# Wheel_speed_tester_rev1.net
KiCad netlist of a schematic drawn in EAGLE
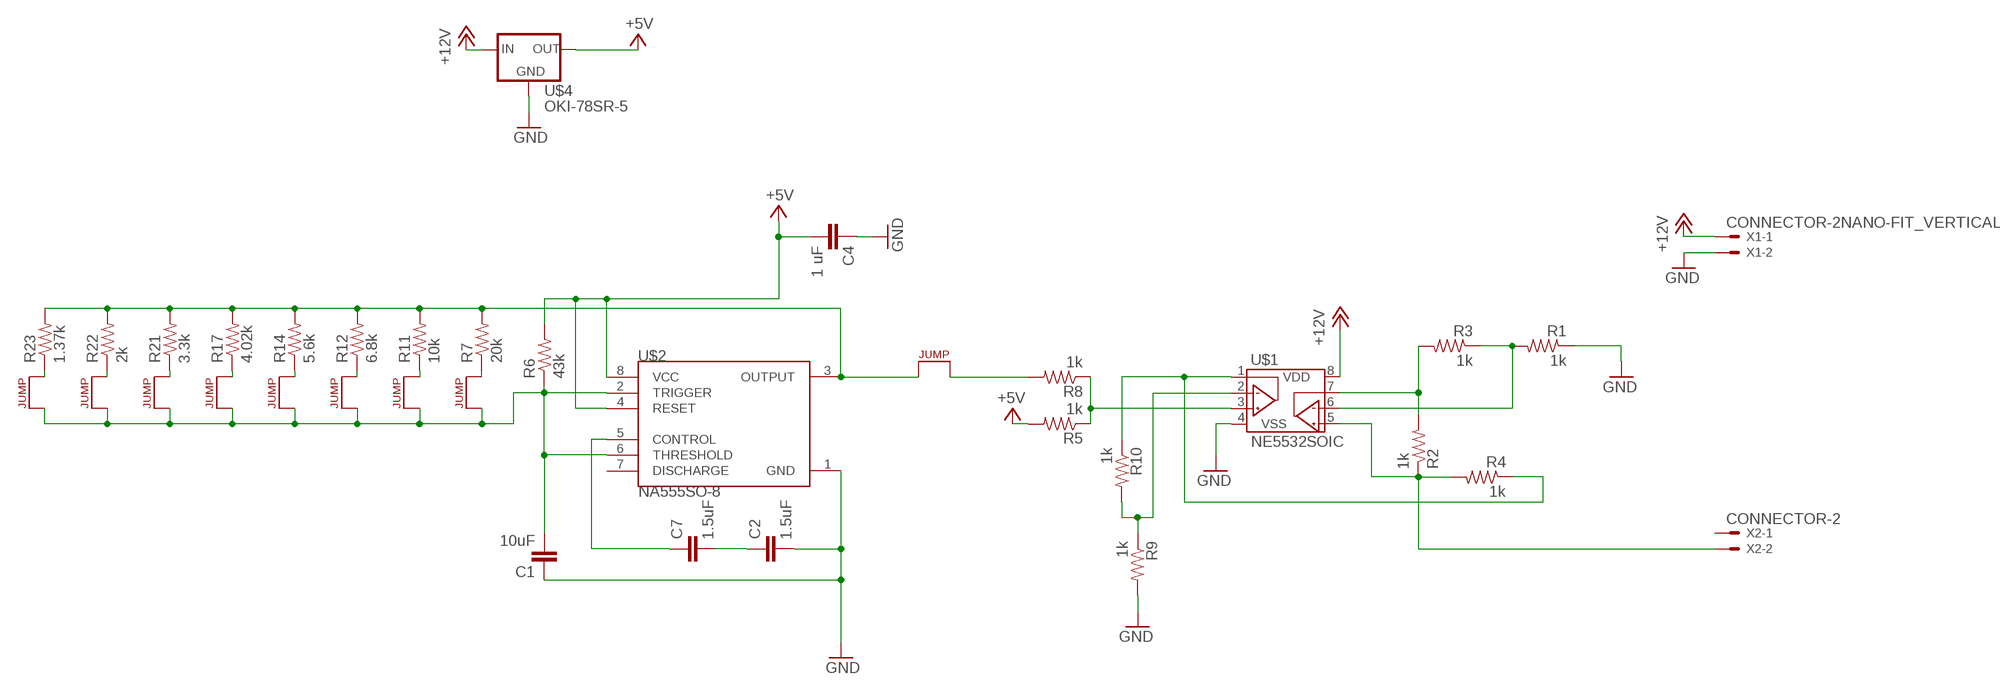
[diagram p0: schematic, sheet 1, part 1 of 2]
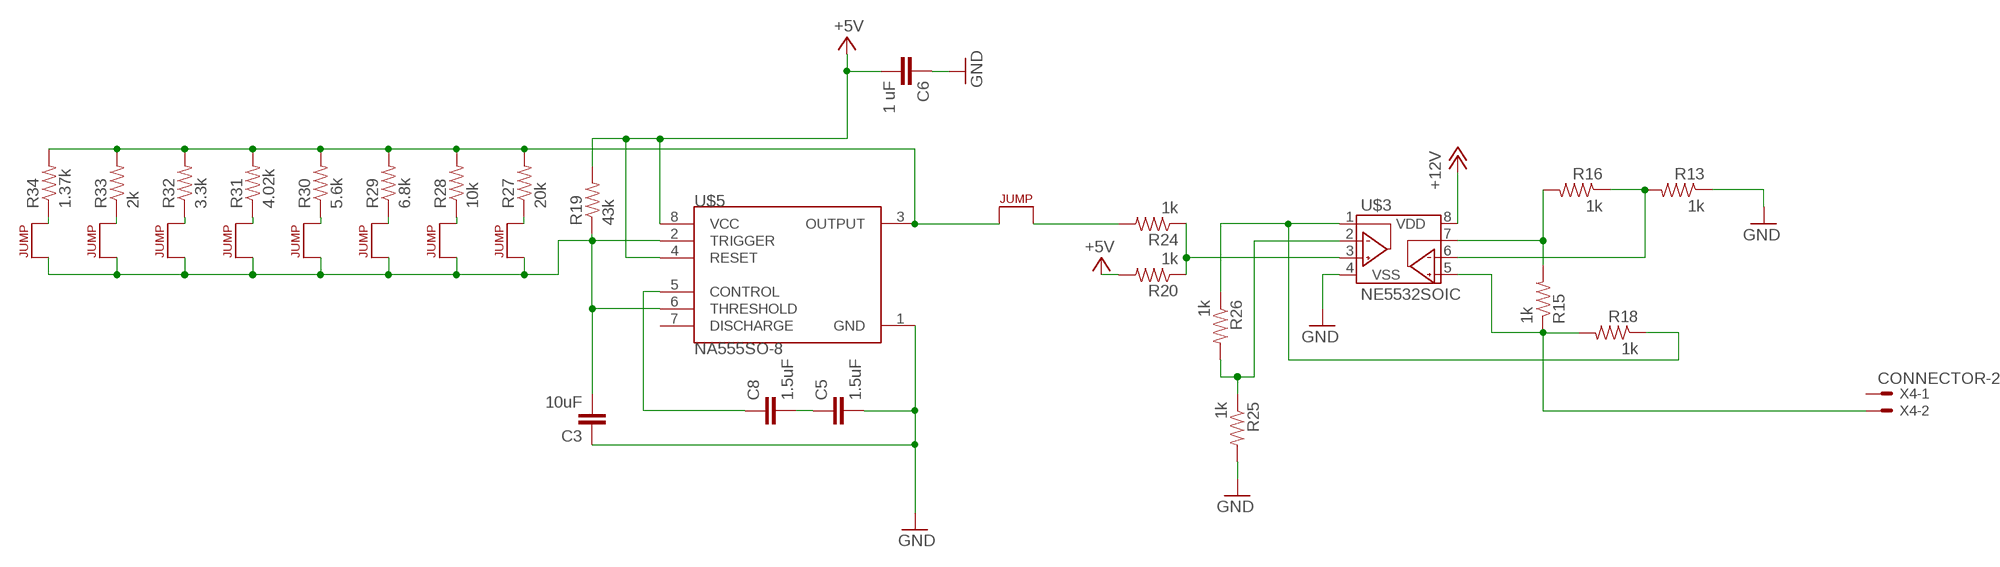
[diagram p1: schematic, sheet 1, part 2 of 2]

(export (version "E")
  (design (tool "Eeschema 10.0.6"))
  (components
    (comp (ref "C1")
      (value "10uF")
      (footprint "eagle-import:0603-CAP")
      (libsource (lib "eagle-import") (part "CAP0603-CAP"))
    )
    (comp (ref "C2")
      (value "1.5uF")
      (footprint "eagle-import:0603-CAP")
      (libsource (lib "eagle-import") (part "CAP0603-CAP"))
    )
    (comp (ref "C3")
      (value "10uF")
      (footprint "eagle-import:0603-CAP")
      (libsource (lib "eagle-import") (part "CAP0603-CAP"))
    )
    (comp (ref "C4")
      (value "1 uF")
      (footprint "eagle-import:0603-CAP")
      (libsource (lib "eagle-import") (part "CAP0603-CAP"))
    )
    (comp (ref "C5")
      (value "1.5uF")
      (footprint "eagle-import:0603-CAP")
      (libsource (lib "eagle-import") (part "CAP0603-CAP"))
    )
    (comp (ref "C6")
      (value "1 uF")
      (footprint "eagle-import:0603-CAP")
      (libsource (lib "eagle-import") (part "CAP0603-CAP"))
    )
    (comp (ref "C7")
      (value "1.5uF")
      (footprint "eagle-import:0603-CAP")
      (libsource (lib "eagle-import") (part "CAP0603-CAP"))
    )
    (comp (ref "C8")
      (value "1.5uF")
      (footprint "eagle-import:0603-CAP")
      (libsource (lib "eagle-import") (part "CAP0603-CAP"))
    )
    (comp (ref "J1")
      (value "JUMPER.1")
      (footprint "eagle-import:1X02")
      (libsource (lib "eagle-import") (part "JUMPER.1"))
    )
    (comp (ref "J2")
      (value "JUMPER.1")
      (footprint "eagle-import:1X02")
      (libsource (lib "eagle-import") (part "JUMPER.1"))
    )
    (comp (ref "J3")
      (value "JUMPER.1")
      (footprint "eagle-import:1X02")
      (libsource (lib "eagle-import") (part "JUMPER.1"))
    )
    (comp (ref "J4")
      (value "JUMPER.1")
      (footprint "eagle-import:1X02")
      (libsource (lib "eagle-import") (part "JUMPER.1"))
    )
    (comp (ref "J5")
      (value "JUMPER.1")
      (footprint "eagle-import:1X02")
      (libsource (lib "eagle-import") (part "JUMPER.1"))
    )
    (comp (ref "J6")
      (value "JUMPER.1")
      (footprint "eagle-import:1X02")
      (libsource (lib "eagle-import") (part "JUMPER.1"))
    )
    (comp (ref "J7")
      (value "JUMPER.1")
      (footprint "eagle-import:1X02")
      (libsource (lib "eagle-import") (part "JUMPER.1"))
    )
    (comp (ref "J8")
      (value "JUMPER.1")
      (footprint "eagle-import:1X02")
      (libsource (lib "eagle-import") (part "JUMPER.1"))
    )
    (comp (ref "J9")
      (value "JUMPER.1")
      (footprint "eagle-import:1X02")
      (libsource (lib "eagle-import") (part "JUMPER.1"))
    )
    (comp (ref "J10")
      (value "JUMPER.1")
      (footprint "eagle-import:1X02")
      (libsource (lib "eagle-import") (part "JUMPER.1"))
    )
    (comp (ref "J11")
      (value "JUMPER.1")
      (footprint "eagle-import:1X02")
      (libsource (lib "eagle-import") (part "JUMPER.1"))
    )
    (comp (ref "J12")
      (value "JUMPER.1")
      (footprint "eagle-import:1X02")
      (libsource (lib "eagle-import") (part "JUMPER.1"))
    )
    (comp (ref "J13")
      (value "JUMPER.1")
      (footprint "eagle-import:1X02")
      (libsource (lib "eagle-import") (part "JUMPER.1"))
    )
    (comp (ref "J14")
      (value "JUMPER.1")
      (footprint "eagle-import:1X02")
      (libsource (lib "eagle-import") (part "JUMPER.1"))
    )
    (comp (ref "J15")
      (value "JUMPER.1")
      (footprint "eagle-import:1X02")
      (libsource (lib "eagle-import") (part "JUMPER.1"))
    )
    (comp (ref "J16")
      (value "JUMPER.1")
      (footprint "eagle-import:1X02")
      (libsource (lib "eagle-import") (part "JUMPER.1"))
    )
    (comp (ref "J17")
      (value "JUMPER.1")
      (footprint "eagle-import:1X02")
      (libsource (lib "eagle-import") (part "JUMPER.1"))
    )
    (comp (ref "J18")
      (value "JUMPER.1")
      (footprint "eagle-import:1X02")
      (libsource (lib "eagle-import") (part "JUMPER.1"))
    )
    (comp (ref "R1")
      (value "1k")
      (footprint "eagle-import:0603-RES")
      (libsource (lib "eagle-import") (part "RESISTOR0603"))
    )
    (comp (ref "R2")
      (value "1k")
      (footprint "eagle-import:0603-RES")
      (libsource (lib "eagle-import") (part "RESISTOR0603"))
    )
    (comp (ref "R3")
      (value "1k")
      (footprint "eagle-import:0603-RES")
      (libsource (lib "eagle-import") (part "RESISTOR0603"))
    )
    (comp (ref "R4")
      (value "1k")
      (footprint "eagle-import:0603-RES")
      (libsource (lib "eagle-import") (part "RESISTOR0603"))
    )
    (comp (ref "R5")
      (value "1k")
      (footprint "eagle-import:0603-RES")
      (libsource (lib "eagle-import") (part "RESISTOR0603"))
    )
    (comp (ref "R6")
      (value "43k")
      (footprint "eagle-import:0603-RES")
      (libsource (lib "eagle-import") (part "RESISTOR0603"))
    )
    (comp (ref "R7")
      (value "20k")
      (footprint "eagle-import:0603-RES")
      (libsource (lib "eagle-import") (part "RESISTOR0603"))
    )
    (comp (ref "R8")
      (value "1k")
      (footprint "eagle-import:0603-RES")
      (libsource (lib "eagle-import") (part "RESISTOR0603"))
    )
    (comp (ref "R9")
      (value "1k")
      (footprint "eagle-import:0603-RES")
      (libsource (lib "eagle-import") (part "RESISTOR0603"))
    )
    (comp (ref "R10")
      (value "1k")
      (footprint "eagle-import:0603-RES")
      (libsource (lib "eagle-import") (part "RESISTOR0603"))
    )
    (comp (ref "R11")
      (value "10k")
      (footprint "eagle-import:0603-RES")
      (libsource (lib "eagle-import") (part "RESISTOR0603"))
    )
    (comp (ref "R12")
      (value "6.8k")
      (footprint "eagle-import:0603-RES")
      (libsource (lib "eagle-import") (part "RESISTOR0603"))
    )
    (comp (ref "R13")
      (value "1k")
      (footprint "eagle-import:0603-RES")
      (libsource (lib "eagle-import") (part "RESISTOR0603"))
    )
    (comp (ref "R14")
      (value "5.6k")
      (footprint "eagle-import:0603-RES")
      (libsource (lib "eagle-import") (part "RESISTOR0603"))
    )
    (comp (ref "R15")
      (value "1k")
      (footprint "eagle-import:0603-RES")
      (libsource (lib "eagle-import") (part "RESISTOR0603"))
    )
    (comp (ref "R16")
      (value "1k")
      (footprint "eagle-import:0603-RES")
      (libsource (lib "eagle-import") (part "RESISTOR0603"))
    )
    (comp (ref "R17")
      (value "4.02k")
      (footprint "eagle-import:0603-RES")
      (libsource (lib "eagle-import") (part "RESISTOR0603"))
    )
    (comp (ref "R18")
      (value "1k")
      (footprint "eagle-import:0603-RES")
      (libsource (lib "eagle-import") (part "RESISTOR0603"))
    )
    (comp (ref "R19")
      (value "43k")
      (footprint "eagle-import:0603-RES")
      (libsource (lib "eagle-import") (part "RESISTOR0603"))
    )
    (comp (ref "R20")
      (value "1k")
      (footprint "eagle-import:0603-RES")
      (libsource (lib "eagle-import") (part "RESISTOR0603"))
    )
    (comp (ref "R21")
      (value "3.3k")
      (footprint "eagle-import:0603-RES")
      (libsource (lib "eagle-import") (part "RESISTOR0603"))
    )
    (comp (ref "R22")
      (value "2k")
      (footprint "eagle-import:0603-RES")
      (libsource (lib "eagle-import") (part "RESISTOR0603"))
    )
    (comp (ref "R23")
      (value "1.37k")
      (footprint "eagle-import:0603-RES")
      (libsource (lib "eagle-import") (part "RESISTOR0603"))
    )
    (comp (ref "R24")
      (value "1k")
      (footprint "eagle-import:0603-RES")
      (libsource (lib "eagle-import") (part "RESISTOR0603"))
    )
    (comp (ref "R25")
      (value "1k")
      (footprint "eagle-import:0603-RES")
      (libsource (lib "eagle-import") (part "RESISTOR0603"))
    )
    (comp (ref "R26")
      (value "1k")
      (footprint "eagle-import:0603-RES")
      (libsource (lib "eagle-import") (part "RESISTOR0603"))
    )
    (comp (ref "R27")
      (value "20k")
      (footprint "eagle-import:0603-RES")
      (libsource (lib "eagle-import") (part "RESISTOR0603"))
    )
    (comp (ref "R28")
      (value "10k")
      (footprint "eagle-import:0603-RES")
      (libsource (lib "eagle-import") (part "RESISTOR0603"))
    )
    (comp (ref "R29")
      (value "6.8k")
      (footprint "eagle-import:0603-RES")
      (libsource (lib "eagle-import") (part "RESISTOR0603"))
    )
    (comp (ref "R30")
      (value "5.6k")
      (footprint "eagle-import:0603-RES")
      (libsource (lib "eagle-import") (part "RESISTOR0603"))
    )
    (comp (ref "R31")
      (value "4.02k")
      (footprint "eagle-import:0603-RES")
      (libsource (lib "eagle-import") (part "RESISTOR0603"))
    )
    (comp (ref "R32")
      (value "3.3k")
      (footprint "eagle-import:0603-RES")
      (libsource (lib "eagle-import") (part "RESISTOR0603"))
    )
    (comp (ref "R33")
      (value "2k")
      (footprint "eagle-import:0603-RES")
      (libsource (lib "eagle-import") (part "RESISTOR0603"))
    )
    (comp (ref "R34")
      (value "1.37k")
      (footprint "eagle-import:0603-RES")
      (libsource (lib "eagle-import") (part "RESISTOR0603"))
    )
    (comp (ref "U$1")
      (value "NE5532SOIC")
      (footprint "eagle-import:SOIC-08")
      (libsource (lib "eagle-import") (part "NE5532SOIC"))
    )
    (comp (ref "U$2")
      (value "NA555SO-8")
      (footprint "eagle-import:SOIC-08")
      (libsource (lib "eagle-import") (part "NA555SO-8"))
    )
    (comp (ref "U$3")
      (value "NE5532SOIC")
      (footprint "eagle-import:SOIC-08")
      (libsource (lib "eagle-import") (part "NE5532SOIC"))
    )
    (comp (ref "U$4")
      (value "OKI-78SR-5")
      (footprint "eagle-import:OKI-78SR")
      (libsource (lib "eagle-import") (part "OKI-78SR-5"))
    )
    (comp (ref "U$5")
      (value "NA555SO-8")
      (footprint "eagle-import:SOIC-08")
      (libsource (lib "eagle-import") (part "NA555SO-8"))
    )
    (comp (ref "X1")
      (value "CONNECTOR-2NANO-FIT_VERTICAL-2")
      (footprint "eagle-import:NANO-FIT_VERTICAL-2")
      (libsource (lib "eagle-import") (part "CONNECTOR-2NANO-FIT_VERTICAL-2"))
    )
    (comp (ref "X2")
      (value "CONNECTOR-2")
      (footprint "eagle-import:MINIFIT_5566-2")
      (libsource (lib "eagle-import") (part "CONNECTOR-2"))
    )
    (comp (ref "X4")
      (value "CONNECTOR-2")
      (footprint "eagle-import:MINIFIT_5566-2")
      (libsource (lib "eagle-import") (part "CONNECTOR-2"))
    )
  )
  (nets
    (net (code "1") (name "+5V") (class "Default")
      (node (ref "C4") (pin "2") (pinfunction "2_2") (pintype "passive"))
      (node (ref "C6") (pin "2") (pinfunction "2_2") (pintype "passive"))
      (node (ref "R19") (pin "2") (pinfunction "2_2") (pintype "passive"))
      (node (ref "R20") (pin "2") (pinfunction "2_2") (pintype "passive"))
      (node (ref "R5") (pin "2") (pinfunction "2_2") (pintype "passive"))
      (node (ref "R6") (pin "2") (pinfunction "2_2") (pintype "passive"))
      (node (ref "U$2") (pin "4") (pinfunction "RESET_4") (pintype "passive"))
      (node (ref "U$2") (pin "8") (pinfunction "VCC_8") (pintype "passive"))
      (node (ref "U$4") (pin "3") (pinfunction "OUT_3") (pintype "output"))
      (node (ref "U$5") (pin "4") (pinfunction "RESET_4") (pintype "passive"))
      (node (ref "U$5") (pin "8") (pinfunction "VCC_8") (pintype "passive"))
    )
    (net (code "2") (name "+12V") (class "Default")
      (node (ref "U$1") (pin "8") (pinfunction "VDD_8") (pintype "passive"))
      (node (ref "U$3") (pin "8") (pinfunction "VDD_8") (pintype "passive"))
      (node (ref "U$4") (pin "1") (pinfunction "IN_1") (pintype "input"))
      (node (ref "X1") (pin "P$1") (pinfunction "S_P$1") (pintype "passive"))
    )
    (net (code "3") (name "GND") (class "Default")
      (node (ref "C1") (pin "1") (pinfunction "1_1") (pintype "passive"))
      (node (ref "C2") (pin "2") (pinfunction "2_2") (pintype "passive"))
      (node (ref "C3") (pin "1") (pinfunction "1_1") (pintype "passive"))
      (node (ref "C4") (pin "1") (pinfunction "1_1") (pintype "passive"))
      (node (ref "C5") (pin "2") (pinfunction "2_2") (pintype "passive"))
      (node (ref "C6") (pin "1") (pinfunction "1_1") (pintype "passive"))
      (node (ref "R1") (pin "1") (pinfunction "1_1") (pintype "passive"))
      (node (ref "R13") (pin "1") (pinfunction "1_1") (pintype "passive"))
      (node (ref "R25") (pin "2") (pinfunction "2_2") (pintype "passive"))
      (node (ref "R9") (pin "2") (pinfunction "2_2") (pintype "passive"))
      (node (ref "U$1") (pin "4") (pinfunction "VSS_4") (pintype "passive"))
      (node (ref "U$2") (pin "1") (pinfunction "GND_1") (pintype "passive"))
      (node (ref "U$3") (pin "4") (pinfunction "VSS_4") (pintype "passive"))
      (node (ref "U$4") (pin "2") (pinfunction "GND_2") (pintype "input"))
      (node (ref "U$5") (pin "1") (pinfunction "GND_1") (pintype "passive"))
      (node (ref "X1") (pin "P$2") (pinfunction "S_P$2") (pintype "passive"))
    )
    (net (code "4") (name "Net-(C2-Pad1)") (class "Default")
      (node (ref "C2") (pin "1") (pinfunction "1_1") (pintype "passive"))
      (node (ref "C7") (pin "2") (pinfunction "2_2") (pintype "passive"))
    )
    (net (code "5") (name "Net-(C5-Pad1)") (class "Default")
      (node (ref "C5") (pin "1") (pinfunction "1_1") (pintype "passive"))
      (node (ref "C8") (pin "2") (pinfunction "2_2") (pintype "passive"))
    )
    (net (code "6") (name "Net-(J1-P$1)") (class "Default")
      (node (ref "C1") (pin "2") (pinfunction "2_2") (pintype "passive"))
      (node (ref "J1") (pin "1") (pinfunction "P$1_1") (pintype "bidirectional"))
      (node (ref "J3") (pin "1") (pinfunction "P$1_1") (pintype "bidirectional"))
      (node (ref "J4") (pin "1") (pinfunction "P$1_1") (pintype "bidirectional"))
      (node (ref "J5") (pin "1") (pinfunction "P$1_1") (pintype "bidirectional"))
      (node (ref "J6") (pin "1") (pinfunction "P$1_1") (pintype "bidirectional"))
      (node (ref "J7") (pin "1") (pinfunction "P$1_1") (pintype "bidirectional"))
      (node (ref "J8") (pin "1") (pinfunction "P$1_1") (pintype "bidirectional"))
      (node (ref "J9") (pin "1") (pinfunction "P$1_1") (pintype "bidirectional"))
      (node (ref "R6") (pin "1") (pinfunction "1_1") (pintype "passive"))
      (node (ref "U$2") (pin "2") (pinfunction "TRIGGER_2") (pintype "passive"))
      (node (ref "U$2") (pin "6") (pinfunction "THRESHOLD_6") (pintype "passive"))
    )
    (net (code "7") (name "Net-(J1-P$2)") (class "Default")
      (node (ref "J1") (pin "2") (pinfunction "P$2_2") (pintype "bidirectional"))
      (node (ref "R23") (pin "1") (pinfunction "1_1") (pintype "passive"))
    )
    (net (code "8") (name "Net-(J2-P$1)") (class "Default")
      (node (ref "J2") (pin "1") (pinfunction "P$1_1") (pintype "bidirectional"))
      (node (ref "R11") (pin "2") (pinfunction "2_2") (pintype "passive"))
      (node (ref "R12") (pin "2") (pinfunction "2_2") (pintype "passive"))
      (node (ref "R14") (pin "2") (pinfunction "2_2") (pintype "passive"))
      (node (ref "R17") (pin "2") (pinfunction "2_2") (pintype "passive"))
      (node (ref "R21") (pin "2") (pinfunction "2_2") (pintype "passive"))
      (node (ref "R22") (pin "2") (pinfunction "2_2") (pintype "passive"))
      (node (ref "R23") (pin "2") (pinfunction "2_2") (pintype "passive"))
      (node (ref "R7") (pin "2") (pinfunction "2_2") (pintype "passive"))
      (node (ref "U$2") (pin "3") (pinfunction "OUTPUT_3") (pintype "passive"))
    )
    (net (code "9") (name "Net-(J2-P$2)") (class "Default")
      (node (ref "J2") (pin "2") (pinfunction "P$2_2") (pintype "bidirectional"))
      (node (ref "R8") (pin "2") (pinfunction "2_2") (pintype "passive"))
    )
    (net (code "10") (name "Net-(J3-P$2)") (class "Default")
      (node (ref "J3") (pin "2") (pinfunction "P$2_2") (pintype "bidirectional"))
      (node (ref "R22") (pin "1") (pinfunction "1_1") (pintype "passive"))
    )
    (net (code "11") (name "Net-(J4-P$2)") (class "Default")
      (node (ref "J4") (pin "2") (pinfunction "P$2_2") (pintype "bidirectional"))
      (node (ref "R21") (pin "1") (pinfunction "1_1") (pintype "passive"))
    )
    (net (code "12") (name "Net-(J5-P$2)") (class "Default")
      (node (ref "J5") (pin "2") (pinfunction "P$2_2") (pintype "bidirectional"))
      (node (ref "R17") (pin "1") (pinfunction "1_1") (pintype "passive"))
    )
    (net (code "13") (name "Net-(J6-P$2)") (class "Default")
      (node (ref "J6") (pin "2") (pinfunction "P$2_2") (pintype "bidirectional"))
      (node (ref "R14") (pin "1") (pinfunction "1_1") (pintype "passive"))
    )
    (net (code "14") (name "Net-(J7-P$2)") (class "Default")
      (node (ref "J7") (pin "2") (pinfunction "P$2_2") (pintype "bidirectional"))
      (node (ref "R12") (pin "1") (pinfunction "1_1") (pintype "passive"))
    )
    (net (code "15") (name "Net-(J8-P$2)") (class "Default")
      (node (ref "J8") (pin "2") (pinfunction "P$2_2") (pintype "bidirectional"))
      (node (ref "R11") (pin "1") (pinfunction "1_1") (pintype "passive"))
    )
    (net (code "16") (name "Net-(J9-P$2)") (class "Default")
      (node (ref "J9") (pin "2") (pinfunction "P$2_2") (pintype "bidirectional"))
      (node (ref "R7") (pin "1") (pinfunction "1_1") (pintype "passive"))
    )
    (net (code "17") (name "Net-(J10-P$1)") (class "Default")
      (node (ref "J10") (pin "1") (pinfunction "P$1_1") (pintype "bidirectional"))
      (node (ref "R27") (pin "2") (pinfunction "2_2") (pintype "passive"))
      (node (ref "R28") (pin "2") (pinfunction "2_2") (pintype "passive"))
      (node (ref "R29") (pin "2") (pinfunction "2_2") (pintype "passive"))
      (node (ref "R30") (pin "2") (pinfunction "2_2") (pintype "passive"))
      (node (ref "R31") (pin "2") (pinfunction "2_2") (pintype "passive"))
      (node (ref "R32") (pin "2") (pinfunction "2_2") (pintype "passive"))
      (node (ref "R33") (pin "2") (pinfunction "2_2") (pintype "passive"))
      (node (ref "R34") (pin "2") (pinfunction "2_2") (pintype "passive"))
      (node (ref "U$5") (pin "3") (pinfunction "OUTPUT_3") (pintype "passive"))
    )
    (net (code "18") (name "Net-(J10-P$2)") (class "Default")
      (node (ref "J10") (pin "2") (pinfunction "P$2_2") (pintype "bidirectional"))
      (node (ref "R24") (pin "2") (pinfunction "2_2") (pintype "passive"))
    )
    (net (code "19") (name "Net-(J11-P$1)") (class "Default")
      (node (ref "C3") (pin "2") (pinfunction "2_2") (pintype "passive"))
      (node (ref "J11") (pin "1") (pinfunction "P$1_1") (pintype "bidirectional"))
      (node (ref "J12") (pin "1") (pinfunction "P$1_1") (pintype "bidirectional"))
      (node (ref "J13") (pin "1") (pinfunction "P$1_1") (pintype "bidirectional"))
      (node (ref "J14") (pin "1") (pinfunction "P$1_1") (pintype "bidirectional"))
      (node (ref "J15") (pin "1") (pinfunction "P$1_1") (pintype "bidirectional"))
      (node (ref "J16") (pin "1") (pinfunction "P$1_1") (pintype "bidirectional"))
      (node (ref "J17") (pin "1") (pinfunction "P$1_1") (pintype "bidirectional"))
      (node (ref "J18") (pin "1") (pinfunction "P$1_1") (pintype "bidirectional"))
      (node (ref "R19") (pin "1") (pinfunction "1_1") (pintype "passive"))
      (node (ref "U$5") (pin "2") (pinfunction "TRIGGER_2") (pintype "passive"))
      (node (ref "U$5") (pin "6") (pinfunction "THRESHOLD_6") (pintype "passive"))
    )
    (net (code "20") (name "Net-(J11-P$2)") (class "Default")
      (node (ref "J11") (pin "2") (pinfunction "P$2_2") (pintype "bidirectional"))
      (node (ref "R34") (pin "1") (pinfunction "1_1") (pintype "passive"))
    )
    (net (code "21") (name "Net-(J12-P$2)") (class "Default")
      (node (ref "J12") (pin "2") (pinfunction "P$2_2") (pintype "bidirectional"))
      (node (ref "R33") (pin "1") (pinfunction "1_1") (pintype "passive"))
    )
    (net (code "22") (name "Net-(J13-P$2)") (class "Default")
      (node (ref "J13") (pin "2") (pinfunction "P$2_2") (pintype "bidirectional"))
      (node (ref "R32") (pin "1") (pinfunction "1_1") (pintype "passive"))
    )
    (net (code "23") (name "Net-(J14-P$2)") (class "Default")
      (node (ref "J14") (pin "2") (pinfunction "P$2_2") (pintype "bidirectional"))
      (node (ref "R31") (pin "1") (pinfunction "1_1") (pintype "passive"))
    )
    (net (code "24") (name "Net-(J15-P$2)") (class "Default")
      (node (ref "J15") (pin "2") (pinfunction "P$2_2") (pintype "bidirectional"))
      (node (ref "R30") (pin "1") (pinfunction "1_1") (pintype "passive"))
    )
    (net (code "25") (name "Net-(J16-P$2)") (class "Default")
      (node (ref "J16") (pin "2") (pinfunction "P$2_2") (pintype "bidirectional"))
      (node (ref "R29") (pin "1") (pinfunction "1_1") (pintype "passive"))
    )
    (net (code "26") (name "Net-(J17-P$2)") (class "Default")
      (node (ref "J17") (pin "2") (pinfunction "P$2_2") (pintype "bidirectional"))
      (node (ref "R28") (pin "1") (pinfunction "1_1") (pintype "passive"))
    )
    (net (code "27") (name "Net-(J18-P$2)") (class "Default")
      (node (ref "J18") (pin "2") (pinfunction "P$2_2") (pintype "bidirectional"))
      (node (ref "R27") (pin "1") (pinfunction "1_1") (pintype "passive"))
    )
    (net (code "28") (name "Net-(U$1-VINA+)") (class "Default")
      (node (ref "R5") (pin "1") (pinfunction "1_1") (pintype "passive"))
      (node (ref "R8") (pin "1") (pinfunction "1_1") (pintype "passive"))
      (node (ref "U$1") (pin "3") (pinfunction "VINA+_3") (pintype "passive"))
    )
    (net (code "29") (name "Net-(U$1-VINA-)") (class "Default")
      (node (ref "R10") (pin "2") (pinfunction "2_2") (pintype "passive"))
      (node (ref "R9") (pin "1") (pinfunction "1_1") (pintype "passive"))
      (node (ref "U$1") (pin "2") (pinfunction "VINA-_2") (pintype "passive"))
    )
    (net (code "30") (name "Net-(U$1-VINB+)") (class "Default")
      (node (ref "R2") (pin "1") (pinfunction "1_1") (pintype "passive"))
      (node (ref "R4") (pin "2") (pinfunction "2_2") (pintype "passive"))
      (node (ref "U$1") (pin "5") (pinfunction "VINB+_5") (pintype "passive"))
      (node (ref "X2") (pin "2") (pinfunction "S_2") (pintype "passive"))
    )
    (net (code "31") (name "Net-(U$1-VINB-)") (class "Default")
      (node (ref "R1") (pin "2") (pinfunction "2_2") (pintype "passive"))
      (node (ref "R3") (pin "1") (pinfunction "1_1") (pintype "passive"))
      (node (ref "U$1") (pin "6") (pinfunction "VINB-_6") (pintype "passive"))
    )
    (net (code "32") (name "Net-(U$1-VOUTA)") (class "Default")
      (node (ref "R10") (pin "1") (pinfunction "1_1") (pintype "passive"))
      (node (ref "R4") (pin "1") (pinfunction "1_1") (pintype "passive"))
      (node (ref "U$1") (pin "1") (pinfunction "VOUTA_1") (pintype "passive"))
    )
    (net (code "33") (name "Net-(U$1-VOUTB)") (class "Default")
      (node (ref "R2") (pin "2") (pinfunction "2_2") (pintype "passive"))
      (node (ref "R3") (pin "2") (pinfunction "2_2") (pintype "passive"))
      (node (ref "U$1") (pin "7") (pinfunction "VOUTB_7") (pintype "passive"))
    )
    (net (code "34") (name "Net-(U$2-CONTROL)") (class "Default")
      (node (ref "C7") (pin "1") (pinfunction "1_1") (pintype "passive"))
      (node (ref "U$2") (pin "5") (pinfunction "CONTROL_5") (pintype "passive"))
    )
    (net (code "35") (name "Net-(U$3-VINA+)") (class "Default")
      (node (ref "R20") (pin "1") (pinfunction "1_1") (pintype "passive"))
      (node (ref "R24") (pin "1") (pinfunction "1_1") (pintype "passive"))
      (node (ref "U$3") (pin "3") (pinfunction "VINA+_3") (pintype "passive"))
    )
    (net (code "36") (name "Net-(U$3-VINA-)") (class "Default")
      (node (ref "R25") (pin "1") (pinfunction "1_1") (pintype "passive"))
      (node (ref "R26") (pin "2") (pinfunction "2_2") (pintype "passive"))
      (node (ref "U$3") (pin "2") (pinfunction "VINA-_2") (pintype "passive"))
    )
    (net (code "37") (name "Net-(U$3-VINB+)") (class "Default")
      (node (ref "R15") (pin "1") (pinfunction "1_1") (pintype "passive"))
      (node (ref "R18") (pin "2") (pinfunction "2_2") (pintype "passive"))
      (node (ref "U$3") (pin "5") (pinfunction "VINB+_5") (pintype "passive"))
      (node (ref "X4") (pin "2") (pinfunction "S_2") (pintype "passive"))
    )
    (net (code "38") (name "Net-(U$3-VINB-)") (class "Default")
      (node (ref "R13") (pin "2") (pinfunction "2_2") (pintype "passive"))
      (node (ref "R16") (pin "1") (pinfunction "1_1") (pintype "passive"))
      (node (ref "U$3") (pin "6") (pinfunction "VINB-_6") (pintype "passive"))
    )
    (net (code "39") (name "Net-(U$3-VOUTA)") (class "Default")
      (node (ref "R18") (pin "1") (pinfunction "1_1") (pintype "passive"))
      (node (ref "R26") (pin "1") (pinfunction "1_1") (pintype "passive"))
      (node (ref "U$3") (pin "1") (pinfunction "VOUTA_1") (pintype "passive"))
    )
    (net (code "40") (name "Net-(U$3-VOUTB)") (class "Default")
      (node (ref "R15") (pin "2") (pinfunction "2_2") (pintype "passive"))
      (node (ref "R16") (pin "2") (pinfunction "2_2") (pintype "passive"))
      (node (ref "U$3") (pin "7") (pinfunction "VOUTB_7") (pintype "passive"))
    )
    (net (code "41") (name "Net-(U$5-CONTROL)") (class "Default")
      (node (ref "C8") (pin "1") (pinfunction "1_1") (pintype "passive"))
      (node (ref "U$5") (pin "5") (pinfunction "CONTROL_5") (pintype "passive"))
    )
    (net (code "42") (name "unconnected-(U$2-DISCHARGE-Pad7)") (class "Default")
      (node (ref "U$2") (pin "7") (pinfunction "DISCHARGE_7") (pintype "passive"))
    )
    (net (code "43") (name "unconnected-(U$5-DISCHARGE-Pad7)") (class "Default")
      (node (ref "U$5") (pin "7") (pinfunction "DISCHARGE_7") (pintype "passive"))
    )
    (net (code "44") (name "unconnected-(X2A-S-Pad1)") (class "Default")
      (node (ref "X2") (pin "1") (pinfunction "S_1") (pintype "passive"))
    )
    (net (code "45") (name "unconnected-(X4A-S-Pad1)") (class "Default")
      (node (ref "X4") (pin "1") (pinfunction "S_1") (pintype "passive"))
    )
  )
)
